# MainBoard_V100_PSU_5V.net
KiCad netlist of a schematic drawn in Altium Designer
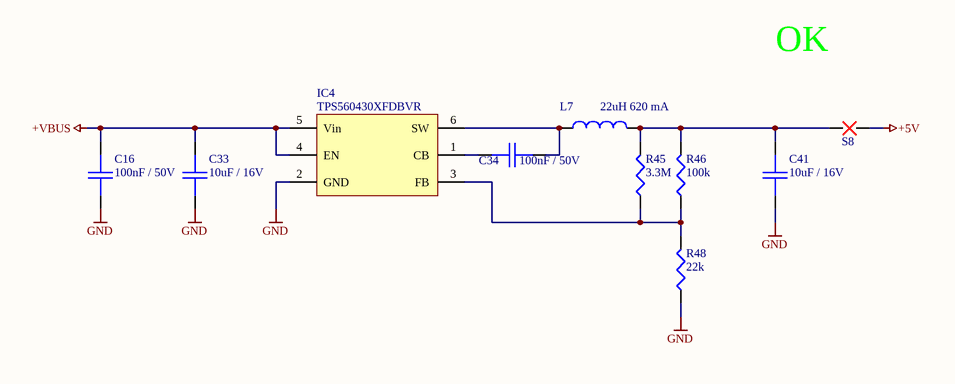
[diagram p0: MainBoard_V100_PSU_5V.SchDoc]

(export (version "E")
  (design (tool "Eeschema 10.0.6"))
  (components
    (comp (ref "C16")
      (value "100nF / 50V")
      (footprint "0805_C")
      (description "100nF 50V X7R")
      (fields (field (name "PART NUMBER") "SMD0805-100nF-50V"))
      (libsource (lib "ALTIUM_DB_LIB") (part "CAP_NONPOL"))
    )
    (comp (ref "C33")
      (value "10uF / 16V")
      (footprint "0805_C")
      (description "10uF 16V X5R")
      (fields (field (name "PART NUMBER") "SMD0805-10uF-16V"))
      (libsource (lib "ALTIUM_DB_LIB") (part "CAP_NONPOL"))
    )
    (comp (ref "C34")
      (value "100nF / 50V")
      (footprint "0805_C")
      (description "100nF 50V X7R")
      (fields (field (name "PART NUMBER") "SMD0805-100nF-50V"))
      (libsource (lib "ALTIUM_DB_LIB") (part "CAP_NONPOL"))
    )
    (comp (ref "C41")
      (value "10uF / 16V")
      (footprint "0805_C")
      (description "10uF 16V X5R")
      (fields (field (name "PART NUMBER") "SMD0805-10uF-16V"))
      (libsource (lib "ALTIUM_DB_LIB") (part "CAP_NONPOL"))
    )
    (comp (ref "IC4")
      (value "TPS560430XFDBVR")
      (footprint "SOT-23-6")
      (description "SIMPLE SWITCHER 4-V to 36-V, 600-mA Synchronous Step-Down Converter")
      (libsource (lib "ALTIUM_DB_LIB") (part "TPS560430"))
    )
    (comp (ref "L7")
      (value "22uH 620 mA")
      (footprint "1210")
      (description "22uH 620 mA 1210")
      (fields (field (name "PART NUMBER") "CBC3225T220KR"))
      (libsource (lib "ALTIUM_DB_LIB") (part "INDUCTOR"))
    )
    (comp (ref "R45")
      (value "3.3M")
      (footprint "0805")
      (description "3.3M 0805 0.125W 5%")
      (fields (field (name "PART NUMBER") "SMD0805-3.3M 5%"))
      (libsource (lib "ALTIUM_DB_LIB") (part "RESISTOR"))
    )
    (comp (ref "R46")
      (value "100k")
      (footprint "0805")
      (description "100k 0805 0.125W 5%")
      (fields (field (name "PART NUMBER") "SMD0805-100k 5%"))
      (libsource (lib "ALTIUM_DB_LIB") (part "RESISTOR"))
    )
    (comp (ref "R48")
      (value "22k")
      (footprint "0805")
      (description "22k 0805 0.1W 5%")
      (fields (field (name "PART NUMBER") "SMD0805-22k-5%"))
      (libsource (lib "ALTIUM_DB_LIB") (part "RESISTOR"))
    )
    (comp (ref "S8")
      (value "SPLITER")
      (footprint "SPLITER2_30mil_9mil")
      (description "SPLITER2_30mil_9mil")
      (libsource (lib "ALTIUM_DB_LIB") (part "SPLITER"))
    )
  )
  (nets
    (net (code "1") (name "+5V") (class "Default")
      (node (ref "S8") (pin "2") (pinfunction "2_2") (pintype "passive"))
    )
    (net (code "2") (name "+VBUS") (class "Default")
      (node (ref "C16") (pin "1") (pintype "passive"))
      (node (ref "C33") (pin "1") (pintype "passive"))
      (node (ref "IC4") (pin "4") (pinfunction "EN_4") (pintype "passive"))
      (node (ref "IC4") (pin "5") (pinfunction "Vin_5") (pintype "passive"))
    )
    (net (code "3") (name "GND") (class "Default")
      (node (ref "C16") (pin "2") (pintype "passive"))
      (node (ref "C33") (pin "2") (pintype "passive"))
      (node (ref "C41") (pin "2") (pintype "passive"))
      (node (ref "IC4") (pin "2") (pinfunction "GND_2") (pintype "passive"))
      (node (ref "R48") (pin "1") (pintype "passive"))
    )
    (net (code "4") (name "Net-(C41-Pad1)") (class "Default")
      (node (ref "C41") (pin "1") (pintype "passive"))
      (node (ref "L7") (pin "2") (pinfunction "2_2") (pintype "passive"))
      (node (ref "R45") (pin "2") (pintype "passive"))
      (node (ref "R46") (pin "2") (pintype "passive"))
      (node (ref "S8") (pin "1") (pinfunction "1_1") (pintype "passive"))
    )
    (net (code "5") (name "Net-(IC4-CB)") (class "Default")
      (node (ref "C34") (pin "1") (pintype "passive"))
      (node (ref "IC4") (pin "1") (pinfunction "CB_1") (pintype "passive"))
    )
    (net (code "6") (name "Net-(IC4-FB)") (class "Default")
      (node (ref "IC4") (pin "3") (pinfunction "FB_3") (pintype "passive"))
      (node (ref "R45") (pin "1") (pintype "passive"))
      (node (ref "R46") (pin "1") (pintype "passive"))
      (node (ref "R48") (pin "2") (pintype "passive"))
    )
    (net (code "7") (name "Net-(IC4-SW)") (class "Default")
      (node (ref "C34") (pin "2") (pintype "passive"))
      (node (ref "IC4") (pin "6") (pinfunction "SW_6") (pintype "passive"))
      (node (ref "L7") (pin "1") (pinfunction "1_1") (pintype "passive"))
    )
  )
)
